# StockTicker.net
KiCad netlist of a schematic drawn in EAGLE
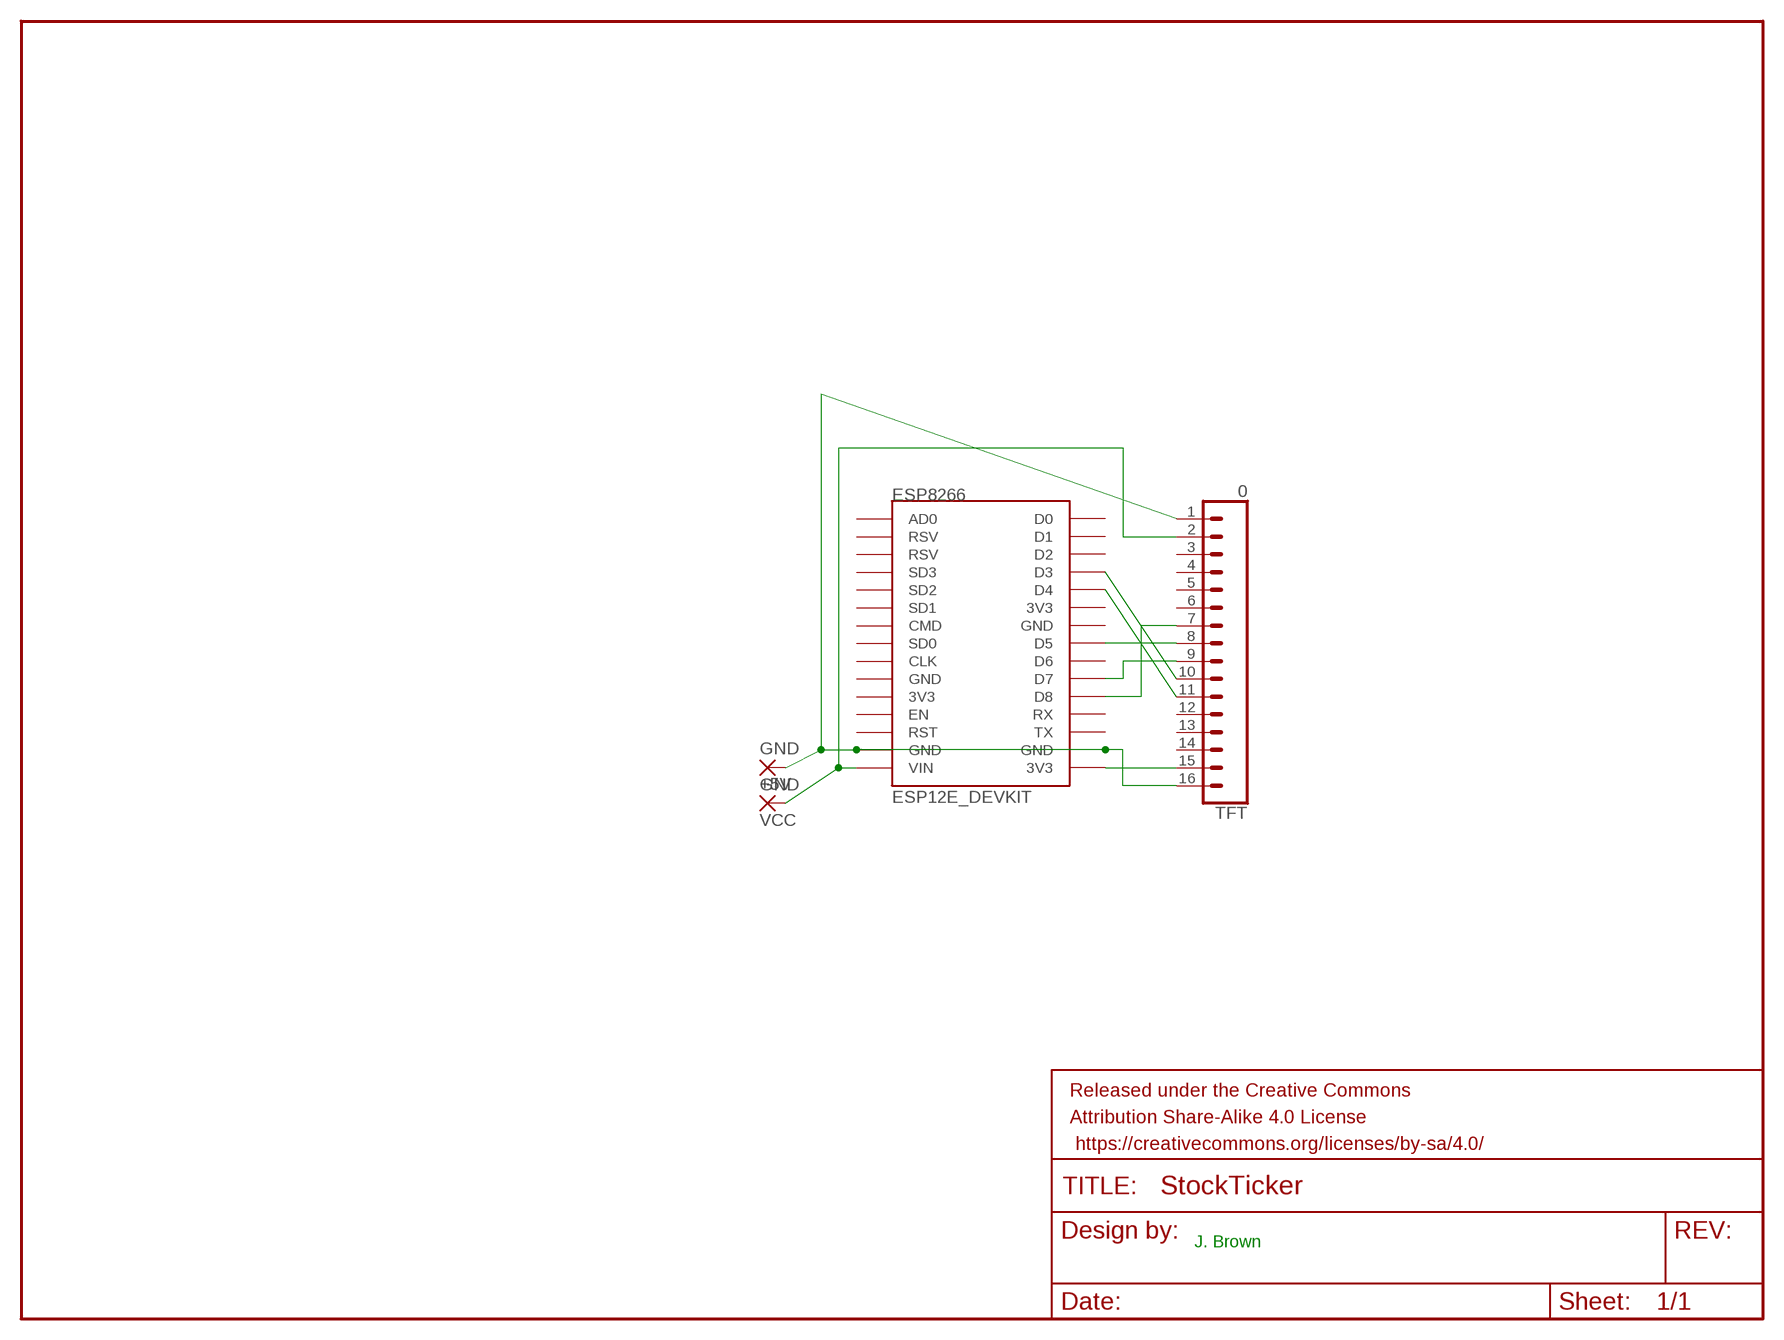
[diagram p0: schematic, sheet 1]

(export (version "E")
  (design (tool "Eeschema 10.0.6"))
  (components
    (comp (ref "+5V")
      (value "VCC")
      (footprint "eagle-import:2,15_1,0")
      (libsource (lib "eagle-import") (part "2,15/1,0"))
    )
    (comp (ref "ESP8266")
      (value "ESP12E_DEVKIT")
      (footprint "eagle-import:ESP12E_DEVKIT")
      (libsource (lib "eagle-import") (part "ESP12E_DEVKIT"))
    )
    (comp (ref "FRAME1")
      (value "FRAME-LETTER")
      (footprint "eagle-import:CREATIVE_COMMONS")
      (libsource (lib "eagle-import") (part "FRAME-LETTER"))
    )
    (comp (ref "GND")
      (value "GND")
      (footprint "eagle-import:2,15_1,0")
      (libsource (lib "eagle-import") (part "2,15/1,0"))
    )
    (comp (ref "TFT")
      (value "0")
      (footprint "eagle-import:1X16")
      (libsource (lib "eagle-import") (part "CONN_16"))
    )
  )
  (nets
    (net (code "1") (name "Net-(+5V-P)") (class "Default")
      (node (ref "+5V") (pin "1") (pinfunction "P_1") (pintype "passive"))
      (node (ref "ESP8266") (pin "VIN") (pinfunction "VIN_VIN") (pintype "bidirectional"))
      (node (ref "TFT") (pin "2") (pinfunction "2_2") (pintype "passive"))
    )
    (net (code "2") (name "Net-(ESP8266-3V3-Pad3V3@2)") (class "Default")
      (node (ref "ESP8266") (pin "3V3@2") (pinfunction "3V3_3V3@2") (pintype "bidirectional"))
      (node (ref "TFT") (pin "15") (pinfunction "15_15") (pintype "passive"))
    )
    (net (code "3") (name "Net-(ESP8266-PadD3)") (class "Default")
      (node (ref "ESP8266") (pin "D3") (pinfunction "D3_D3") (pintype "bidirectional"))
      (node (ref "TFT") (pin "10") (pinfunction "10_10") (pintype "passive"))
    )
    (net (code "4") (name "Net-(ESP8266-PadD4)") (class "Default")
      (node (ref "ESP8266") (pin "D4") (pinfunction "D4_D4") (pintype "bidirectional"))
      (node (ref "TFT") (pin "11") (pinfunction "11_11") (pintype "passive"))
    )
    (net (code "5") (name "Net-(ESP8266-PadD5)") (class "Default")
      (node (ref "ESP8266") (pin "D5") (pinfunction "D5_D5") (pintype "bidirectional"))
      (node (ref "TFT") (pin "8") (pinfunction "8_8") (pintype "passive"))
    )
    (net (code "6") (name "Net-(ESP8266-PadD7)") (class "Default")
      (node (ref "ESP8266") (pin "D7") (pinfunction "D7_D7") (pintype "bidirectional"))
      (node (ref "TFT") (pin "9") (pinfunction "9_9") (pintype "passive"))
    )
    (net (code "7") (name "Net-(ESP8266-PadD8)") (class "Default")
      (node (ref "ESP8266") (pin "D8") (pinfunction "D8_D8") (pintype "bidirectional"))
      (node (ref "TFT") (pin "7") (pinfunction "7_7") (pintype "passive"))
    )
    (net (code "8") (name "Net-(GND-P)") (class "Default")
      (node (ref "ESP8266") (pin "GND@1") (pinfunction "GND_GND@1") (pintype "bidirectional"))
      (node (ref "ESP8266") (pin "GND@3") (pinfunction "GND_GND@3") (pintype "bidirectional"))
      (node (ref "GND") (pin "1") (pinfunction "P_1") (pintype "passive"))
      (node (ref "TFT") (pin "1") (pinfunction "1_1") (pintype "passive"))
      (node (ref "TFT") (pin "16") (pinfunction "16_16") (pintype "passive"))
    )
    (net (code "9") (name "unconnected-(ESP8266-3V3-Pad3V3@0)") (class "Default")
      (node (ref "ESP8266") (pin "3V3@0") (pinfunction "3V3_3V3@0") (pintype "bidirectional"))
    )
    (net (code "10") (name "unconnected-(ESP8266-3V3-Pad3V3@1)") (class "Default")
      (node (ref "ESP8266") (pin "3V3@1") (pinfunction "3V3_3V3@1") (pintype "bidirectional"))
    )
    (net (code "11") (name "unconnected-(ESP8266-GND-PadGND@0)") (class "Default")
      (node (ref "ESP8266") (pin "GND@0") (pinfunction "GND_GND@0") (pintype "bidirectional"))
    )
    (net (code "12") (name "unconnected-(ESP8266-GND-PadGND@2)") (class "Default")
      (node (ref "ESP8266") (pin "GND@2") (pinfunction "GND_GND@2") (pintype "bidirectional"))
    )
    (net (code "13") (name "unconnected-(ESP8266-PadAD0)") (class "Default")
      (node (ref "ESP8266") (pin "AD0") (pinfunction "AD0_AD0") (pintype "bidirectional"))
    )
    (net (code "14") (name "unconnected-(ESP8266-PadCLK)") (class "Default")
      (node (ref "ESP8266") (pin "CLK") (pinfunction "CLK_CLK") (pintype "bidirectional"))
    )
    (net (code "15") (name "unconnected-(ESP8266-PadCMD)") (class "Default")
      (node (ref "ESP8266") (pin "CMD") (pinfunction "CMD_CMD") (pintype "bidirectional"))
    )
    (net (code "16") (name "unconnected-(ESP8266-PadD0)") (class "Default")
      (node (ref "ESP8266") (pin "D0") (pinfunction "D0_D0") (pintype "bidirectional"))
    )
    (net (code "17") (name "unconnected-(ESP8266-PadD1)") (class "Default")
      (node (ref "ESP8266") (pin "D1") (pinfunction "D1_D1") (pintype "bidirectional"))
    )
    (net (code "18") (name "unconnected-(ESP8266-PadD2)") (class "Default")
      (node (ref "ESP8266") (pin "D2") (pinfunction "D2_D2") (pintype "bidirectional"))
    )
    (net (code "19") (name "unconnected-(ESP8266-PadD6)") (class "Default")
      (node (ref "ESP8266") (pin "D6") (pinfunction "D6_D6") (pintype "bidirectional"))
    )
    (net (code "20") (name "unconnected-(ESP8266-PadEN)") (class "Default")
      (node (ref "ESP8266") (pin "EN") (pinfunction "EN_EN") (pintype "bidirectional"))
    )
    (net (code "21") (name "unconnected-(ESP8266-PadRST)") (class "Default")
      (node (ref "ESP8266") (pin "RST") (pinfunction "RST_RST") (pintype "bidirectional"))
    )
    (net (code "22") (name "unconnected-(ESP8266-PadRX)") (class "Default")
      (node (ref "ESP8266") (pin "RX") (pinfunction "RX_RX") (pintype "bidirectional"))
    )
    (net (code "23") (name "unconnected-(ESP8266-PadSD0)") (class "Default")
      (node (ref "ESP8266") (pin "SD0") (pinfunction "SD0_SD0") (pintype "bidirectional"))
    )
    (net (code "24") (name "unconnected-(ESP8266-PadSD1)") (class "Default")
      (node (ref "ESP8266") (pin "SD1") (pinfunction "SD1_SD1") (pintype "bidirectional"))
    )
    (net (code "25") (name "unconnected-(ESP8266-PadSD2)") (class "Default")
      (node (ref "ESP8266") (pin "SD2") (pinfunction "SD2_SD2") (pintype "bidirectional"))
    )
    (net (code "26") (name "unconnected-(ESP8266-PadSD3)") (class "Default")
      (node (ref "ESP8266") (pin "SD3") (pinfunction "SD3_SD3") (pintype "bidirectional"))
    )
    (net (code "27") (name "unconnected-(ESP8266-PadTX)") (class "Default")
      (node (ref "ESP8266") (pin "TX") (pinfunction "TX_TX") (pintype "bidirectional"))
    )
    (net (code "28") (name "unconnected-(ESP8266-RSV-PadRSV@0)") (class "Default")
      (node (ref "ESP8266") (pin "RSV@0") (pinfunction "RSV_RSV@0") (pintype "bidirectional"))
    )
    (net (code "29") (name "unconnected-(ESP8266-RSV-PadRSV@1)") (class "Default")
      (node (ref "ESP8266") (pin "RSV@1") (pinfunction "RSV_RSV@1") (pintype "bidirectional"))
    )
    (net (code "30") (name "unconnected-(TFT-Pad3)") (class "Default")
      (node (ref "TFT") (pin "3") (pinfunction "3_3") (pintype "passive"))
    )
    (net (code "31") (name "unconnected-(TFT-Pad4)") (class "Default")
      (node (ref "TFT") (pin "4") (pinfunction "4_4") (pintype "passive"))
    )
    (net (code "32") (name "unconnected-(TFT-Pad5)") (class "Default")
      (node (ref "TFT") (pin "5") (pinfunction "5_5") (pintype "passive"))
    )
    (net (code "33") (name "unconnected-(TFT-Pad6)") (class "Default")
      (node (ref "TFT") (pin "6") (pinfunction "6_6") (pintype "passive"))
    )
    (net (code "34") (name "unconnected-(TFT-Pad12)") (class "Default")
      (node (ref "TFT") (pin "12") (pinfunction "12_12") (pintype "passive"))
    )
    (net (code "35") (name "unconnected-(TFT-Pad13)") (class "Default")
      (node (ref "TFT") (pin "13") (pinfunction "13_13") (pintype "passive"))
    )
    (net (code "36") (name "unconnected-(TFT-Pad14)") (class "Default")
      (node (ref "TFT") (pin "14") (pinfunction "14_14") (pintype "passive"))
    )
  )
)
